# working.net
KiCad netlist of a schematic drawn in EAGLE
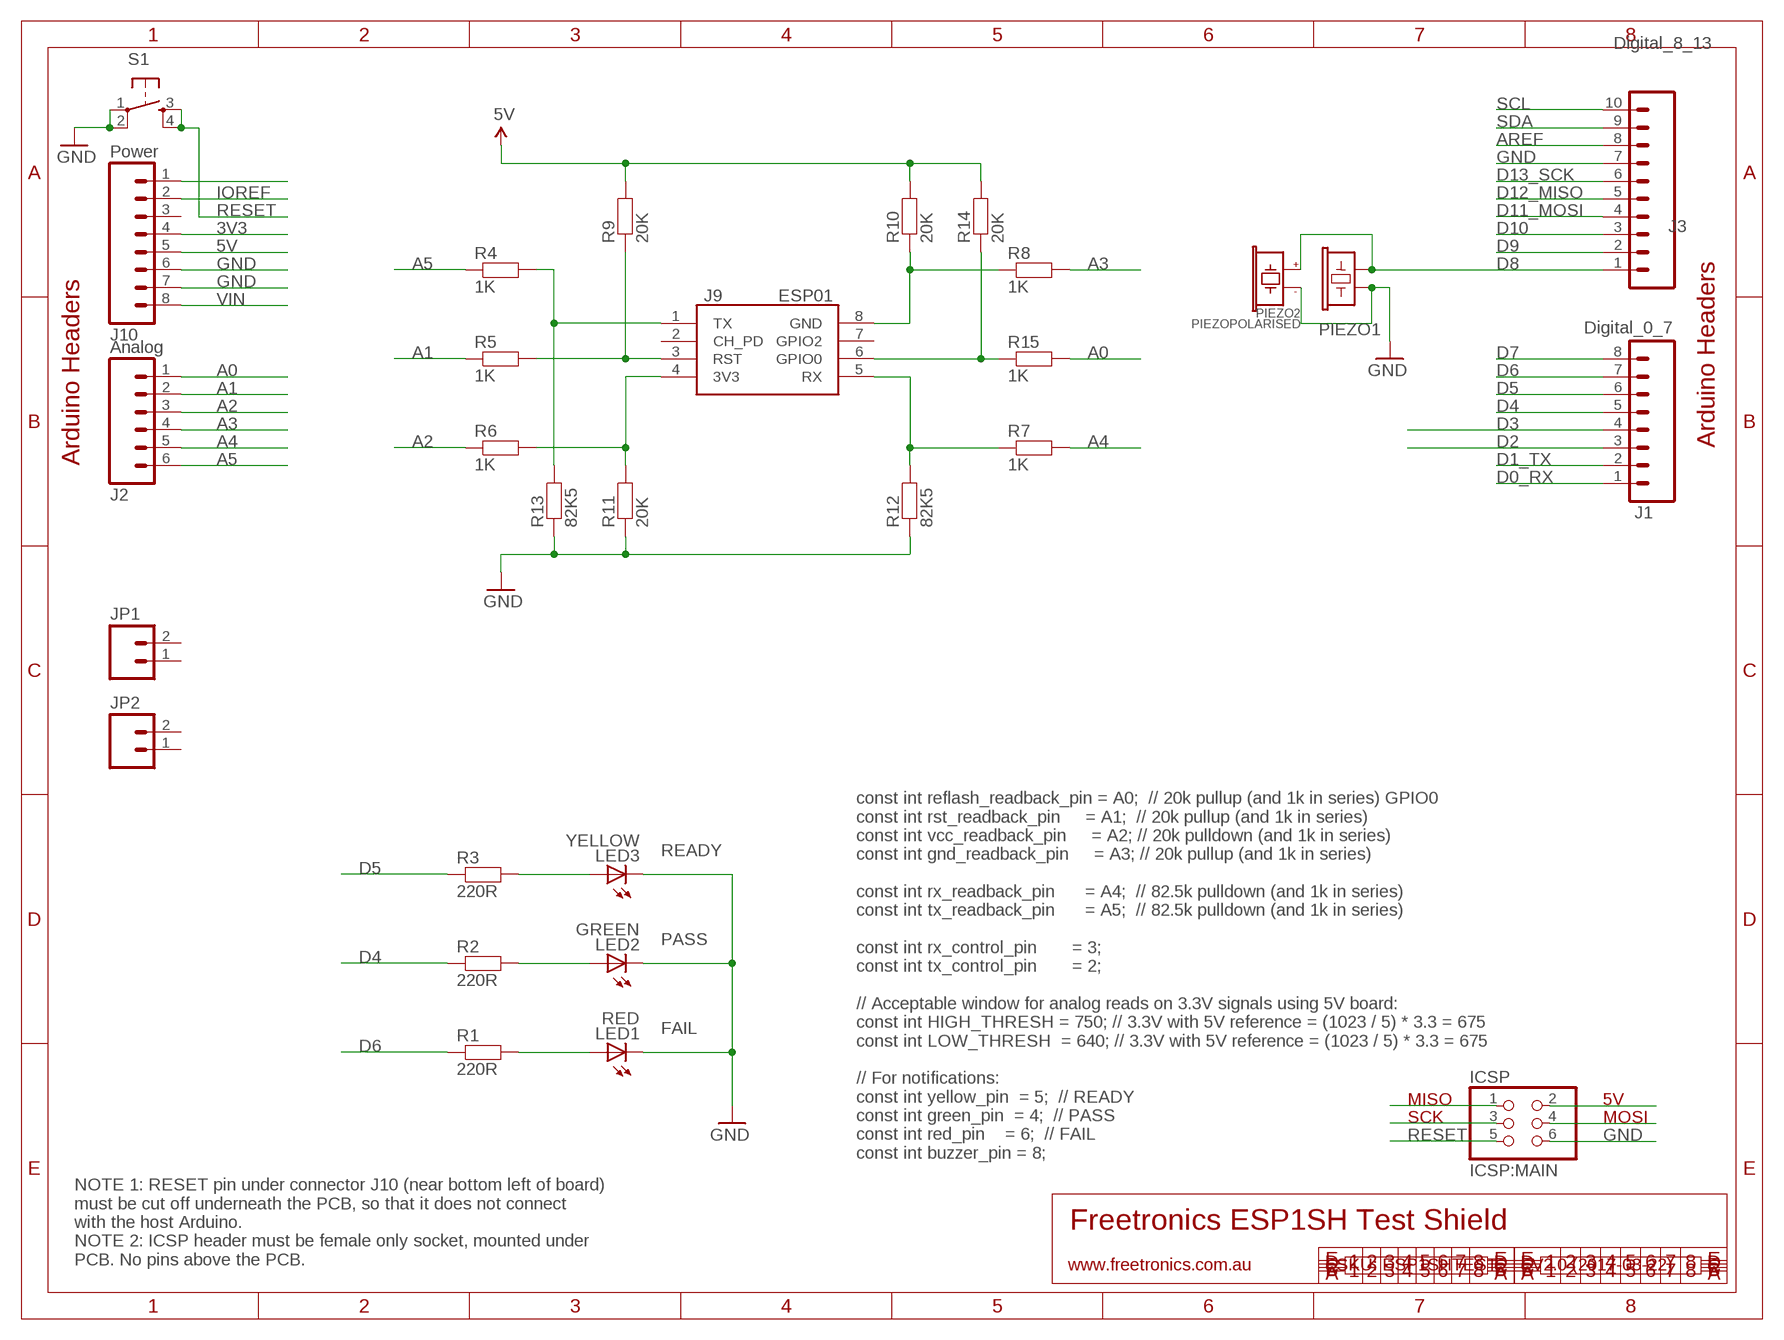
[diagram p0: schematic, sheet 1]

(export (version "E")
  (design (tool "Eeschema 10.0.6"))
  (components
    (comp (ref "ICSP")
      (value "ICSP:MAIN")
      (footprint "eagle-import:2X03")
      (libsource (lib "eagle-import") (part "PINHD-2X3"))
    )
    (comp (ref "J1")
      (value "Digital_0_7")
      (footprint "eagle-import:1X08")
      (libsource (lib "eagle-import") (part "M08"))
    )
    (comp (ref "J2")
      (value "Analog")
      (footprint "eagle-import:1X06")
      (libsource (lib "eagle-import") (part "M06SIP"))
    )
    (comp (ref "J3")
      (value "Digital_8_13")
      (footprint "eagle-import:1X10")
      (libsource (lib "eagle-import") (part "M100.1"))
    )
    (comp (ref "J9")
      (value "ESP01")
      (footprint "eagle-import:ESP01")
      (libsource (lib "eagle-import") (part "ESP01"))
    )
    (comp (ref "J10")
      (value "Power")
      (footprint "eagle-import:1X08")
      (libsource (lib "eagle-import") (part "freetronics-master-v1_M08"))
    )
    (comp (ref "JP1")
      (value "M02PTH")
      (footprint "eagle-import:1X02")
      (libsource (lib "eagle-import") (part "M02PTH"))
    )
    (comp (ref "JP2")
      (value "M02PTH")
      (footprint "eagle-import:1X02")
      (libsource (lib "eagle-import") (part "M02PTH"))
    )
    (comp (ref "LED1")
      (value "RED")
      (footprint "eagle-import:LED-0603")
      (libsource (lib "eagle-import") (part "LED0603"))
    )
    (comp (ref "LED2")
      (value "GREEN")
      (footprint "eagle-import:LED-0603")
      (libsource (lib "eagle-import") (part "LED0603"))
    )
    (comp (ref "LED3")
      (value "YELLOW")
      (footprint "eagle-import:LED-0603")
      (libsource (lib "eagle-import") (part "LED0603"))
    )
    (comp (ref "PIEZO1")
      (value "BUZZERSMD12X12")
      (footprint "eagle-import:BUZZER-12X12-SMT")
      (libsource (lib "eagle-import") (part "BUZZERSMD12X12"))
    )
    (comp (ref "PIEZO2")
      (value "PIEZOPOLARISED")
      (footprint "eagle-import:PIEZO12MMWIDEPOLARISED")
      (libsource (lib "eagle-import") (part "PIEZOPOLARISED"))
    )
    (comp (ref "R1")
      (value "220R")
      (footprint "eagle-import:0603")
      (libsource (lib "eagle-import") (part "RESISTOR0603"))
    )
    (comp (ref "R2")
      (value "220R")
      (footprint "eagle-import:0603")
      (libsource (lib "eagle-import") (part "RESISTOR0603"))
    )
    (comp (ref "R3")
      (value "220R")
      (footprint "eagle-import:0603")
      (libsource (lib "eagle-import") (part "RESISTOR0603"))
    )
    (comp (ref "R4")
      (value "1K")
      (footprint "eagle-import:0603")
      (libsource (lib "eagle-import") (part "RESISTOR0603"))
    )
    (comp (ref "R5")
      (value "1K")
      (footprint "eagle-import:0603")
      (libsource (lib "eagle-import") (part "RESISTOR0603"))
    )
    (comp (ref "R6")
      (value "1K")
      (footprint "eagle-import:0603")
      (libsource (lib "eagle-import") (part "RESISTOR0603"))
    )
    (comp (ref "R7")
      (value "1K")
      (footprint "eagle-import:0603")
      (libsource (lib "eagle-import") (part "RESISTOR0603"))
    )
    (comp (ref "R8")
      (value "1K")
      (footprint "eagle-import:0603")
      (libsource (lib "eagle-import") (part "RESISTOR0603"))
    )
    (comp (ref "R9")
      (value "20K")
      (footprint "eagle-import:0603")
      (libsource (lib "eagle-import") (part "RESISTOR0603"))
    )
    (comp (ref "R10")
      (value "20K")
      (footprint "eagle-import:0603")
      (libsource (lib "eagle-import") (part "RESISTOR0603"))
    )
    (comp (ref "R11")
      (value "20K")
      (footprint "eagle-import:0603")
      (libsource (lib "eagle-import") (part "RESISTOR0603"))
    )
    (comp (ref "R12")
      (value "82K5")
      (footprint "eagle-import:0603")
      (libsource (lib "eagle-import") (part "RESISTOR0603"))
    )
    (comp (ref "R13")
      (value "82K5")
      (footprint "eagle-import:0603")
      (libsource (lib "eagle-import") (part "RESISTOR0603"))
    )
    (comp (ref "R14")
      (value "20K")
      (footprint "eagle-import:0603")
      (libsource (lib "eagle-import") (part "RESISTOR0603"))
    )
    (comp (ref "R15")
      (value "1K")
      (footprint "eagle-import:0603")
      (libsource (lib "eagle-import") (part "RESISTOR0603"))
    )
    (comp (ref "S1")
      (value "TAC_SWITCHPTH")
      (footprint "eagle-import:TACTILE-PTH")
      (libsource (lib "eagle-import") (part "TAC_SWITCHPTH"))
    )
  )
  (nets
    (net (code "1") (name "/3V3") (class "Default")
      (node (ref "J10") (pin "4") (pinfunction "4_4") (pintype "passive"))
    )
    (net (code "2") (name "/A0") (class "Default")
      (node (ref "J2") (pin "1") (pinfunction "1_1") (pintype "passive"))
      (node (ref "R15") (pin "2") (pinfunction "2_2") (pintype "passive"))
    )
    (net (code "3") (name "/A1") (class "Default")
      (node (ref "J2") (pin "2") (pinfunction "2_2") (pintype "passive"))
      (node (ref "R5") (pin "1") (pinfunction "1_1") (pintype "passive"))
    )
    (net (code "4") (name "/A2") (class "Default")
      (node (ref "J2") (pin "3") (pinfunction "3_3") (pintype "passive"))
      (node (ref "R6") (pin "1") (pinfunction "1_1") (pintype "passive"))
    )
    (net (code "5") (name "/A3") (class "Default")
      (node (ref "J2") (pin "4") (pinfunction "4_4") (pintype "passive"))
      (node (ref "R8") (pin "2") (pinfunction "2_2") (pintype "passive"))
    )
    (net (code "6") (name "/A4") (class "Default")
      (node (ref "J2") (pin "5") (pinfunction "5_5") (pintype "passive"))
      (node (ref "R7") (pin "2") (pinfunction "2_2") (pintype "passive"))
    )
    (net (code "7") (name "/A5") (class "Default")
      (node (ref "J2") (pin "6") (pinfunction "6_6") (pintype "passive"))
      (node (ref "R4") (pin "1") (pinfunction "1_1") (pintype "passive"))
    )
    (net (code "8") (name "/AREF") (class "Default")
      (node (ref "J3") (pin "8") (pinfunction "8_8") (pintype "passive"))
    )
    (net (code "9") (name "/D0_RX") (class "Default")
      (node (ref "J1") (pin "1") (pinfunction "1_1") (pintype "passive"))
    )
    (net (code "10") (name "/D1_TX") (class "Default")
      (node (ref "J1") (pin "2") (pinfunction "2_2") (pintype "passive"))
    )
    (net (code "11") (name "/D2") (class "Default")
      (node (ref "J1") (pin "3") (pinfunction "3_3") (pintype "passive"))
    )
    (net (code "12") (name "/D3") (class "Default")
      (node (ref "J1") (pin "4") (pinfunction "4_4") (pintype "passive"))
    )
    (net (code "13") (name "/D4") (class "Default")
      (node (ref "J1") (pin "5") (pinfunction "5_5") (pintype "passive"))
      (node (ref "R2") (pin "1") (pinfunction "1_1") (pintype "passive"))
    )
    (net (code "14") (name "/D5") (class "Default")
      (node (ref "J1") (pin "6") (pinfunction "6_6") (pintype "passive"))
      (node (ref "R3") (pin "1") (pinfunction "1_1") (pintype "passive"))
    )
    (net (code "15") (name "/D6") (class "Default")
      (node (ref "J1") (pin "7") (pinfunction "7_7") (pintype "passive"))
      (node (ref "R1") (pin "1") (pinfunction "1_1") (pintype "passive"))
    )
    (net (code "16") (name "/D7") (class "Default")
      (node (ref "J1") (pin "8") (pinfunction "8_8") (pintype "passive"))
    )
    (net (code "17") (name "/D8") (class "Default")
      (node (ref "J3") (pin "1") (pinfunction "1_1") (pintype "passive"))
      (node (ref "PIEZO1") (pin "1") (pinfunction "1_1") (pintype "passive"))
      (node (ref "PIEZO2") (pin "1") (pinfunction "+_1") (pintype "bidirectional"))
    )
    (net (code "18") (name "/D9") (class "Default")
      (node (ref "J3") (pin "2") (pinfunction "2_2") (pintype "passive"))
    )
    (net (code "19") (name "/D10") (class "Default")
      (node (ref "J3") (pin "3") (pinfunction "3_3") (pintype "passive"))
    )
    (net (code "20") (name "/D11_MOSI") (class "Default")
      (node (ref "J3") (pin "4") (pinfunction "4_4") (pintype "passive"))
    )
    (net (code "21") (name "/D12_MISO") (class "Default")
      (node (ref "J3") (pin "5") (pinfunction "5_5") (pintype "passive"))
    )
    (net (code "22") (name "/D13_SCK") (class "Default")
      (node (ref "J3") (pin "6") (pinfunction "6_6") (pintype "passive"))
    )
    (net (code "23") (name "/IOREF") (class "Default")
      (node (ref "J10") (pin "2") (pinfunction "2_2") (pintype "passive"))
    )
    (net (code "24") (name "/RESET") (class "Default")
      (node (ref "ICSP") (pin "5") (pinfunction "5_5") (pintype "passive"))
      (node (ref "S1") (pin "3") (pinfunction "3_3") (pintype "passive"))
      (node (ref "S1") (pin "4") (pinfunction "4_4") (pintype "passive"))
    )
    (net (code "25") (name "/SCL") (class "Default")
      (node (ref "J3") (pin "10") (pinfunction "10_10") (pintype "passive"))
    )
    (net (code "26") (name "/SDA") (class "Default")
      (node (ref "J3") (pin "9") (pinfunction "9_9") (pintype "passive"))
    )
    (net (code "27") (name "/VIN") (class "Default")
      (node (ref "J10") (pin "8") (pinfunction "8_8") (pintype "passive"))
    )
    (net (code "28") (name "5V") (class "Default")
      (node (ref "J10") (pin "5") (pinfunction "5_5") (pintype "passive"))
      (node (ref "R10") (pin "2") (pinfunction "2_2") (pintype "passive"))
      (node (ref "R14") (pin "2") (pinfunction "2_2") (pintype "passive"))
      (node (ref "R9") (pin "2") (pinfunction "2_2") (pintype "passive"))
    )
    (net (code "29") (name "GND") (class "Default")
      (node (ref "ICSP") (pin "6") (pinfunction "6_6") (pintype "passive"))
      (node (ref "J10") (pin "6") (pinfunction "6_6") (pintype "passive"))
      (node (ref "J10") (pin "7") (pinfunction "7_7") (pintype "passive"))
      (node (ref "J3") (pin "7") (pinfunction "7_7") (pintype "passive"))
      (node (ref "LED1") (pin "C") (pinfunction "C_C") (pintype "passive"))
      (node (ref "LED2") (pin "C") (pinfunction "C_C") (pintype "passive"))
      (node (ref "LED3") (pin "C") (pinfunction "C_C") (pintype "passive"))
      (node (ref "PIEZO1") (pin "2") (pinfunction "2_2") (pintype "passive"))
      (node (ref "PIEZO2") (pin "2") (pinfunction "-_2") (pintype "bidirectional"))
      (node (ref "R11") (pin "1") (pinfunction "1_1") (pintype "passive"))
      (node (ref "R12") (pin "1") (pinfunction "1_1") (pintype "passive"))
      (node (ref "R13") (pin "1") (pinfunction "1_1") (pintype "passive"))
      (node (ref "S1") (pin "1") (pinfunction "1_1") (pintype "passive"))
      (node (ref "S1") (pin "2") (pinfunction "2_2") (pintype "passive"))
    )
    (net (code "30") (name "Net-(J9-3V3)") (class "Default")
      (node (ref "J9") (pin "4") (pinfunction "3V3_4") (pintype "bidirectional"))
      (node (ref "R11") (pin "2") (pinfunction "2_2") (pintype "passive"))
      (node (ref "R6") (pin "2") (pinfunction "2_2") (pintype "passive"))
    )
    (net (code "31") (name "Net-(J9-GND)") (class "Default")
      (node (ref "J9") (pin "8") (pinfunction "GND_8") (pintype "bidirectional"))
      (node (ref "R10") (pin "1") (pinfunction "1_1") (pintype "passive"))
      (node (ref "R8") (pin "1") (pinfunction "1_1") (pintype "passive"))
    )
    (net (code "32") (name "Net-(J9-GPIO0)") (class "Default")
      (node (ref "J9") (pin "6") (pinfunction "GPIO0_6") (pintype "bidirectional"))
      (node (ref "R14") (pin "1") (pinfunction "1_1") (pintype "passive"))
      (node (ref "R15") (pin "1") (pinfunction "1_1") (pintype "passive"))
    )
    (net (code "33") (name "Net-(J9-RST)") (class "Default")
      (node (ref "J9") (pin "3") (pinfunction "RST_3") (pintype "bidirectional"))
      (node (ref "R5") (pin "2") (pinfunction "2_2") (pintype "passive"))
      (node (ref "R9") (pin "1") (pinfunction "1_1") (pintype "passive"))
    )
    (net (code "34") (name "Net-(J9-RX)") (class "Default")
      (node (ref "J9") (pin "5") (pinfunction "RX_5") (pintype "bidirectional"))
      (node (ref "R12") (pin "2") (pinfunction "2_2") (pintype "passive"))
      (node (ref "R7") (pin "1") (pinfunction "1_1") (pintype "passive"))
    )
    (net (code "35") (name "Net-(J9-TX)") (class "Default")
      (node (ref "J9") (pin "1") (pinfunction "TX_1") (pintype "bidirectional"))
      (node (ref "R13") (pin "2") (pinfunction "2_2") (pintype "passive"))
      (node (ref "R4") (pin "2") (pinfunction "2_2") (pintype "passive"))
    )
    (net (code "36") (name "Net-(LED1-PadA)") (class "Default")
      (node (ref "LED1") (pin "A") (pinfunction "A_A") (pintype "passive"))
      (node (ref "R1") (pin "2") (pinfunction "2_2") (pintype "passive"))
    )
    (net (code "37") (name "Net-(LED2-PadA)") (class "Default")
      (node (ref "LED2") (pin "A") (pinfunction "A_A") (pintype "passive"))
      (node (ref "R2") (pin "2") (pinfunction "2_2") (pintype "passive"))
    )
    (net (code "38") (name "Net-(LED3-PadA)") (class "Default")
      (node (ref "LED3") (pin "A") (pinfunction "A_A") (pintype "passive"))
      (node (ref "R3") (pin "2") (pinfunction "2_2") (pintype "passive"))
    )
    (net (code "39") (name "unconnected-(ICSP-Pad1)") (class "Default")
      (node (ref "ICSP") (pin "1") (pinfunction "1_1") (pintype "passive"))
    )
    (net (code "40") (name "unconnected-(ICSP-Pad2)") (class "Default")
      (node (ref "ICSP") (pin "2") (pinfunction "2_2") (pintype "passive"))
    )
    (net (code "41") (name "unconnected-(ICSP-Pad3)") (class "Default")
      (node (ref "ICSP") (pin "3") (pinfunction "3_3") (pintype "passive"))
    )
    (net (code "42") (name "unconnected-(ICSP-Pad4)") (class "Default")
      (node (ref "ICSP") (pin "4") (pinfunction "4_4") (pintype "passive"))
    )
    (net (code "43") (name "unconnected-(J9-CH_PD-Pad2)") (class "Default")
      (node (ref "J9") (pin "2") (pinfunction "CH_PD_2") (pintype "bidirectional"))
    )
    (net (code "44") (name "unconnected-(J9-GPIO2-Pad7)") (class "Default")
      (node (ref "J9") (pin "7") (pinfunction "GPIO2_7") (pintype "bidirectional"))
    )
    (net (code "45") (name "unconnected-(J10-Pad1)") (class "Default")
      (node (ref "J10") (pin "1") (pinfunction "1_1") (pintype "passive"))
    )
    (net (code "46") (name "unconnected-(J10-Pad3)") (class "Default")
      (node (ref "J10") (pin "3") (pinfunction "3_3") (pintype "passive"))
    )
    (net (code "47") (name "unconnected-(JP1-Pad1)") (class "Default")
      (node (ref "JP1") (pin "1") (pinfunction "1_1") (pintype "passive"))
    )
    (net (code "48") (name "unconnected-(JP1-Pad2)") (class "Default")
      (node (ref "JP1") (pin "2") (pinfunction "2_2") (pintype "passive"))
    )
    (net (code "49") (name "unconnected-(JP2-Pad1)") (class "Default")
      (node (ref "JP2") (pin "1") (pinfunction "1_1") (pintype "passive"))
    )
    (net (code "50") (name "unconnected-(JP2-Pad2)") (class "Default")
      (node (ref "JP2") (pin "2") (pinfunction "2_2") (pintype "passive"))
    )
  )
)
